# Capstone_Shield.net
KiCad netlist of a schematic drawn in EAGLE
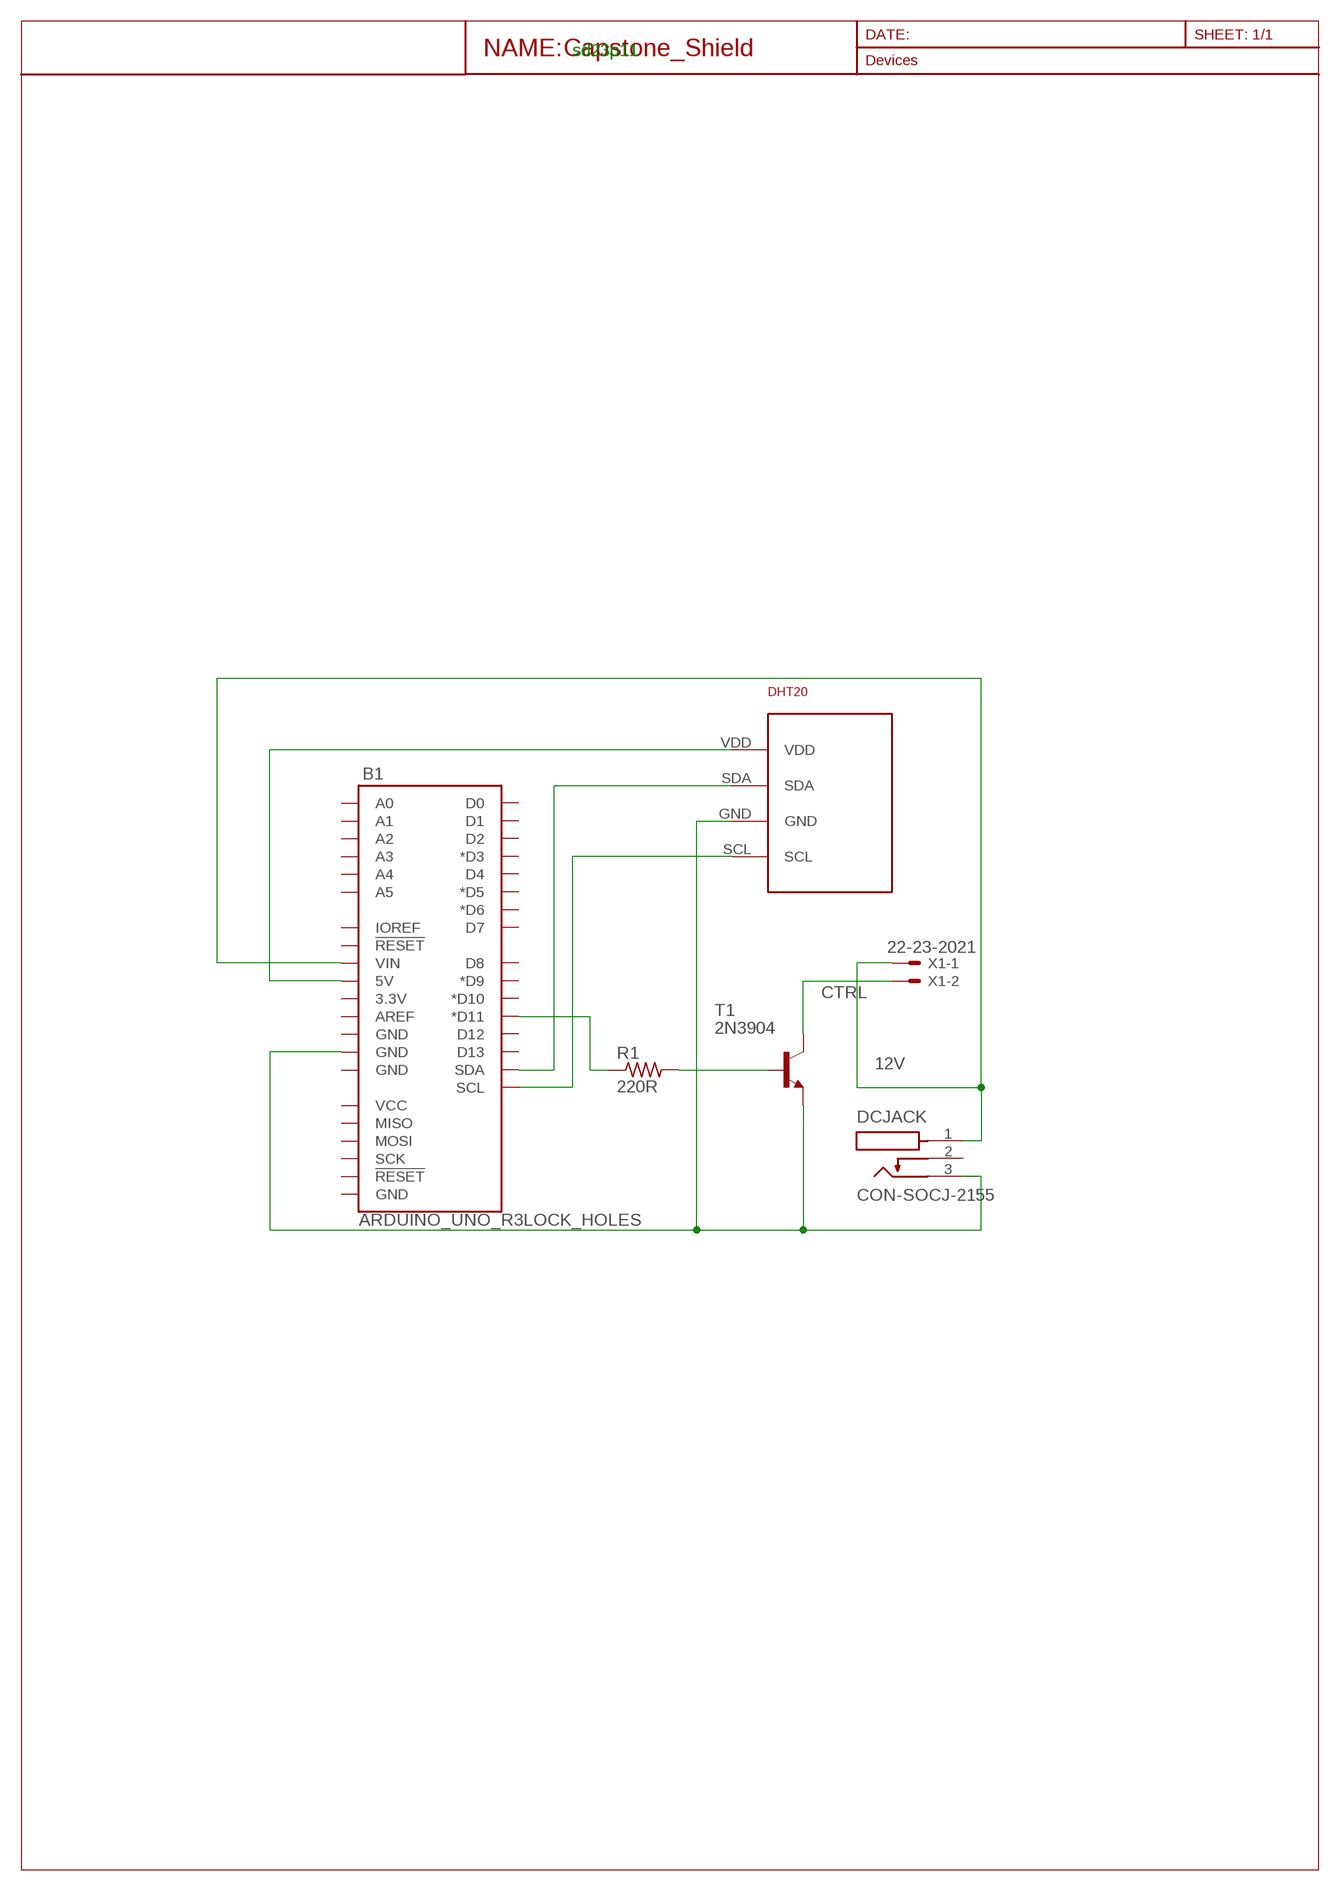
[diagram p0: schematic, sheet 1]

(export (version "E")
  (design (tool "Eeschema 10.0.6"))
  (components
    (comp (ref "B1")
      (value "ARDUINO_UNO_R3LOCK_HOLES")
      (footprint "eagle-import:ARDUINO_R3_LOCK_HOLES")
      (libsource (lib "eagle-import") (part "ARDUINO_UNO_R3LOCK_HOLES"))
    )
    (comp (ref "DCJACK")
      (value "CON-SOCJ-2155")
      (footprint "eagle-import:GRAVITECH_CON-SOCJ-2155")
      (fields (field (name "MF") "Gravitech"))
      (libsource (lib "eagle-import") (part "CON-SOCJ-2155"))
    )
    (comp (ref "R1")
      (value "220R")
      (footprint "eagle-import:0207_10")
      (libsource (lib "eagle-import") (part "R-US_0207/10"))
    )
    (comp (ref "T1")
      (value "2N3904")
      (footprint "eagle-import:TO92")
      (libsource (lib "eagle-import") (part "2N3904"))
    )
    (comp (ref "U$1")
      (value "DHT20THROUGH_HOLE")
      (footprint "eagle-import:DHT20")
      (libsource (lib "eagle-import") (part "DHT20THROUGH_HOLE"))
    )
    (comp (ref "X1")
      (value "22-23-2021")
      (footprint "eagle-import:22-23-2021")
      (fields (field (name "MF") "MOLEX") (field (name "MPN") "FAN"))
      (libsource (lib "eagle-import") (part "22-23-2021"))
    )
  )
  (nets
    (net (code "1") (name "/12V") (class "Default")
      (node (ref "B1") (pin "VIN") (pinfunction "VIN_VIN") (pintype "bidirectional"))
      (node (ref "DCJACK") (pin "1") (pinfunction "1_1") (pintype "passive"))
      (node (ref "X1") (pin "1") (pinfunction "S_1") (pintype "passive"))
    )
    (net (code "2") (name "/CTRL") (class "Default")
      (node (ref "T1") (pin "1") (pinfunction "C_1") (pintype "passive"))
      (node (ref "X1") (pin "2") (pinfunction "S_2") (pintype "passive"))
    )
    (net (code "3") (name "Net-(B1-*D11)") (class "Default")
      (node (ref "B1") (pin "D11") (pinfunction "*D11_D11") (pintype "bidirectional"))
      (node (ref "R1") (pin "1") (pinfunction "1_1") (pintype "passive"))
    )
    (net (code "4") (name "Net-(B1-Pad5V)") (class "Default")
      (node (ref "B1") (pin "5V") (pinfunction "5V_5V") (pintype "bidirectional"))
      (node (ref "U$1") (pin "VDD") (pinfunction "VDD_VDD") (pintype "bidirectional"))
    )
    (net (code "5") (name "Net-(B1-PadSCL)") (class "Default")
      (node (ref "B1") (pin "SCL") (pinfunction "SCL_SCL") (pintype "bidirectional"))
      (node (ref "U$1") (pin "SCL") (pinfunction "SCL_SCL") (pintype "bidirectional"))
    )
    (net (code "6") (name "Net-(B1-PadSDA)") (class "Default")
      (node (ref "B1") (pin "SDA") (pinfunction "SDA_SDA") (pintype "bidirectional"))
      (node (ref "U$1") (pin "SDA") (pinfunction "SDA_SDA") (pintype "bidirectional"))
    )
    (net (code "7") (name "Net-(T1-B)") (class "Default")
      (node (ref "R1") (pin "2") (pinfunction "2_2") (pintype "passive"))
      (node (ref "T1") (pin "2") (pinfunction "B_2") (pintype "passive"))
    )
    (net (code "8") (name "Net-(T1-E)") (class "Default")
      (node (ref "B1") (pin "GND@3") (pinfunction "GND_GND@3") (pintype "bidirectional"))
      (node (ref "DCJACK") (pin "3") (pinfunction "3_3") (pintype "passive"))
      (node (ref "T1") (pin "3") (pinfunction "E_3") (pintype "passive"))
      (node (ref "U$1") (pin "GND") (pinfunction "GND_GND") (pintype "bidirectional"))
    )
    (net (code "9") (name "unconnected-(B1-*D3-PadD3)") (class "Default")
      (node (ref "B1") (pin "D3") (pinfunction "*D3_D3") (pintype "bidirectional"))
    )
    (net (code "10") (name "unconnected-(B1-*D5-PadD5)") (class "Default")
      (node (ref "B1") (pin "D5") (pinfunction "*D5_D5") (pintype "bidirectional"))
    )
    (net (code "11") (name "unconnected-(B1-*D6-PadD6)") (class "Default")
      (node (ref "B1") (pin "D6") (pinfunction "*D6_D6") (pintype "bidirectional"))
    )
    (net (code "12") (name "unconnected-(B1-*D9-PadD9)") (class "Default")
      (node (ref "B1") (pin "D9") (pinfunction "*D9_D9") (pintype "bidirectional"))
    )
    (net (code "13") (name "unconnected-(B1-*D10-PadD10)") (class "Default")
      (node (ref "B1") (pin "D10") (pinfunction "*D10_D10") (pintype "bidirectional"))
    )
    (net (code "14") (name "unconnected-(B1-GND-PadGND@1)") (class "Default")
      (node (ref "B1") (pin "GND@1") (pinfunction "GND_GND@1") (pintype "bidirectional"))
    )
    (net (code "15") (name "unconnected-(B1-GND-PadGND@2)") (class "Default")
      (node (ref "B1") (pin "GND@2") (pinfunction "GND_GND@2") (pintype "bidirectional"))
    )
    (net (code "16") (name "unconnected-(B1-GND-PadGND@4)") (class "Default")
      (node (ref "B1") (pin "GND@4") (pinfunction "GND_GND@4") (pintype "bidirectional"))
    )
    (net (code "17") (name "unconnected-(B1-Pad3.3V)") (class "Default")
      (node (ref "B1") (pin "3.3V") (pinfunction "3.3V_3.3V") (pintype "bidirectional"))
    )
    (net (code "18") (name "unconnected-(B1-PadA0)") (class "Default")
      (node (ref "B1") (pin "A0") (pinfunction "A0_A0") (pintype "bidirectional"))
    )
    (net (code "19") (name "unconnected-(B1-PadA1)") (class "Default")
      (node (ref "B1") (pin "A1") (pinfunction "A1_A1") (pintype "bidirectional"))
    )
    (net (code "20") (name "unconnected-(B1-PadA2)") (class "Default")
      (node (ref "B1") (pin "A2") (pinfunction "A2_A2") (pintype "bidirectional"))
    )
    (net (code "21") (name "unconnected-(B1-PadA3)") (class "Default")
      (node (ref "B1") (pin "A3") (pinfunction "A3_A3") (pintype "bidirectional"))
    )
    (net (code "22") (name "unconnected-(B1-PadA4)") (class "Default")
      (node (ref "B1") (pin "A4") (pinfunction "A4_A4") (pintype "bidirectional"))
    )
    (net (code "23") (name "unconnected-(B1-PadA5)") (class "Default")
      (node (ref "B1") (pin "A5") (pinfunction "A5_A5") (pintype "bidirectional"))
    )
    (net (code "24") (name "unconnected-(B1-PadAREF)") (class "Default")
      (node (ref "B1") (pin "AREF") (pinfunction "AREF_AREF") (pintype "bidirectional"))
    )
    (net (code "25") (name "unconnected-(B1-PadD0)") (class "Default")
      (node (ref "B1") (pin "D0") (pinfunction "D0_D0") (pintype "bidirectional"))
    )
    (net (code "26") (name "unconnected-(B1-PadD1)") (class "Default")
      (node (ref "B1") (pin "D1") (pinfunction "D1_D1") (pintype "bidirectional"))
    )
    (net (code "27") (name "unconnected-(B1-PadD2)") (class "Default")
      (node (ref "B1") (pin "D2") (pinfunction "D2_D2") (pintype "bidirectional"))
    )
    (net (code "28") (name "unconnected-(B1-PadD4)") (class "Default")
      (node (ref "B1") (pin "D4") (pinfunction "D4_D4") (pintype "bidirectional"))
    )
    (net (code "29") (name "unconnected-(B1-PadD7)") (class "Default")
      (node (ref "B1") (pin "D7") (pinfunction "D7_D7") (pintype "bidirectional"))
    )
    (net (code "30") (name "unconnected-(B1-PadD8)") (class "Default")
      (node (ref "B1") (pin "D8") (pinfunction "D8_D8") (pintype "bidirectional"))
    )
    (net (code "31") (name "unconnected-(B1-PadD12)") (class "Default")
      (node (ref "B1") (pin "D12") (pinfunction "D12_D12") (pintype "bidirectional"))
    )
    (net (code "32") (name "unconnected-(B1-PadD13)") (class "Default")
      (node (ref "B1") (pin "D13") (pinfunction "D13_D13") (pintype "bidirectional"))
    )
    (net (code "33") (name "unconnected-(B1-PadIOREF)") (class "Default")
      (node (ref "B1") (pin "IOREF") (pinfunction "IOREF_IOREF") (pintype "bidirectional"))
    )
    (net (code "34") (name "unconnected-(B1-PadMISO)") (class "Default")
      (node (ref "B1") (pin "MISO") (pinfunction "MISO_MISO") (pintype "bidirectional"))
    )
    (net (code "35") (name "unconnected-(B1-PadMOSI)") (class "Default")
      (node (ref "B1") (pin "MOSI") (pinfunction "MOSI_MOSI") (pintype "bidirectional"))
    )
    (net (code "36") (name "unconnected-(B1-PadSCK)") (class "Default")
      (node (ref "B1") (pin "SCK") (pinfunction "SCK_SCK") (pintype "bidirectional"))
    )
    (net (code "37") (name "unconnected-(B1-PadVCC)") (class "Default")
      (node (ref "B1") (pin "VCC") (pinfunction "VCC_VCC") (pintype "bidirectional"))
    )
    (net (code "38") (name "unconnected-(B1-~{RESET}-PadRESET@1)") (class "Default")
      (node (ref "B1") (pin "RESET@1") (pinfunction "~{RESET}_RESET@1") (pintype "bidirectional"))
    )
    (net (code "39") (name "unconnected-(B1-~{RESET}-PadRESET@2)") (class "Default")
      (node (ref "B1") (pin "RESET@2") (pinfunction "~{RESET}_RESET@2") (pintype "bidirectional"))
    )
    (net (code "40") (name "unconnected-(DCJACK-Pad2)") (class "Default")
      (node (ref "DCJACK") (pin "2") (pinfunction "2_2") (pintype "passive"))
    )
  )
)
